# Mimi_layout.net
KiCad netlist of a schematic drawn in EAGLE
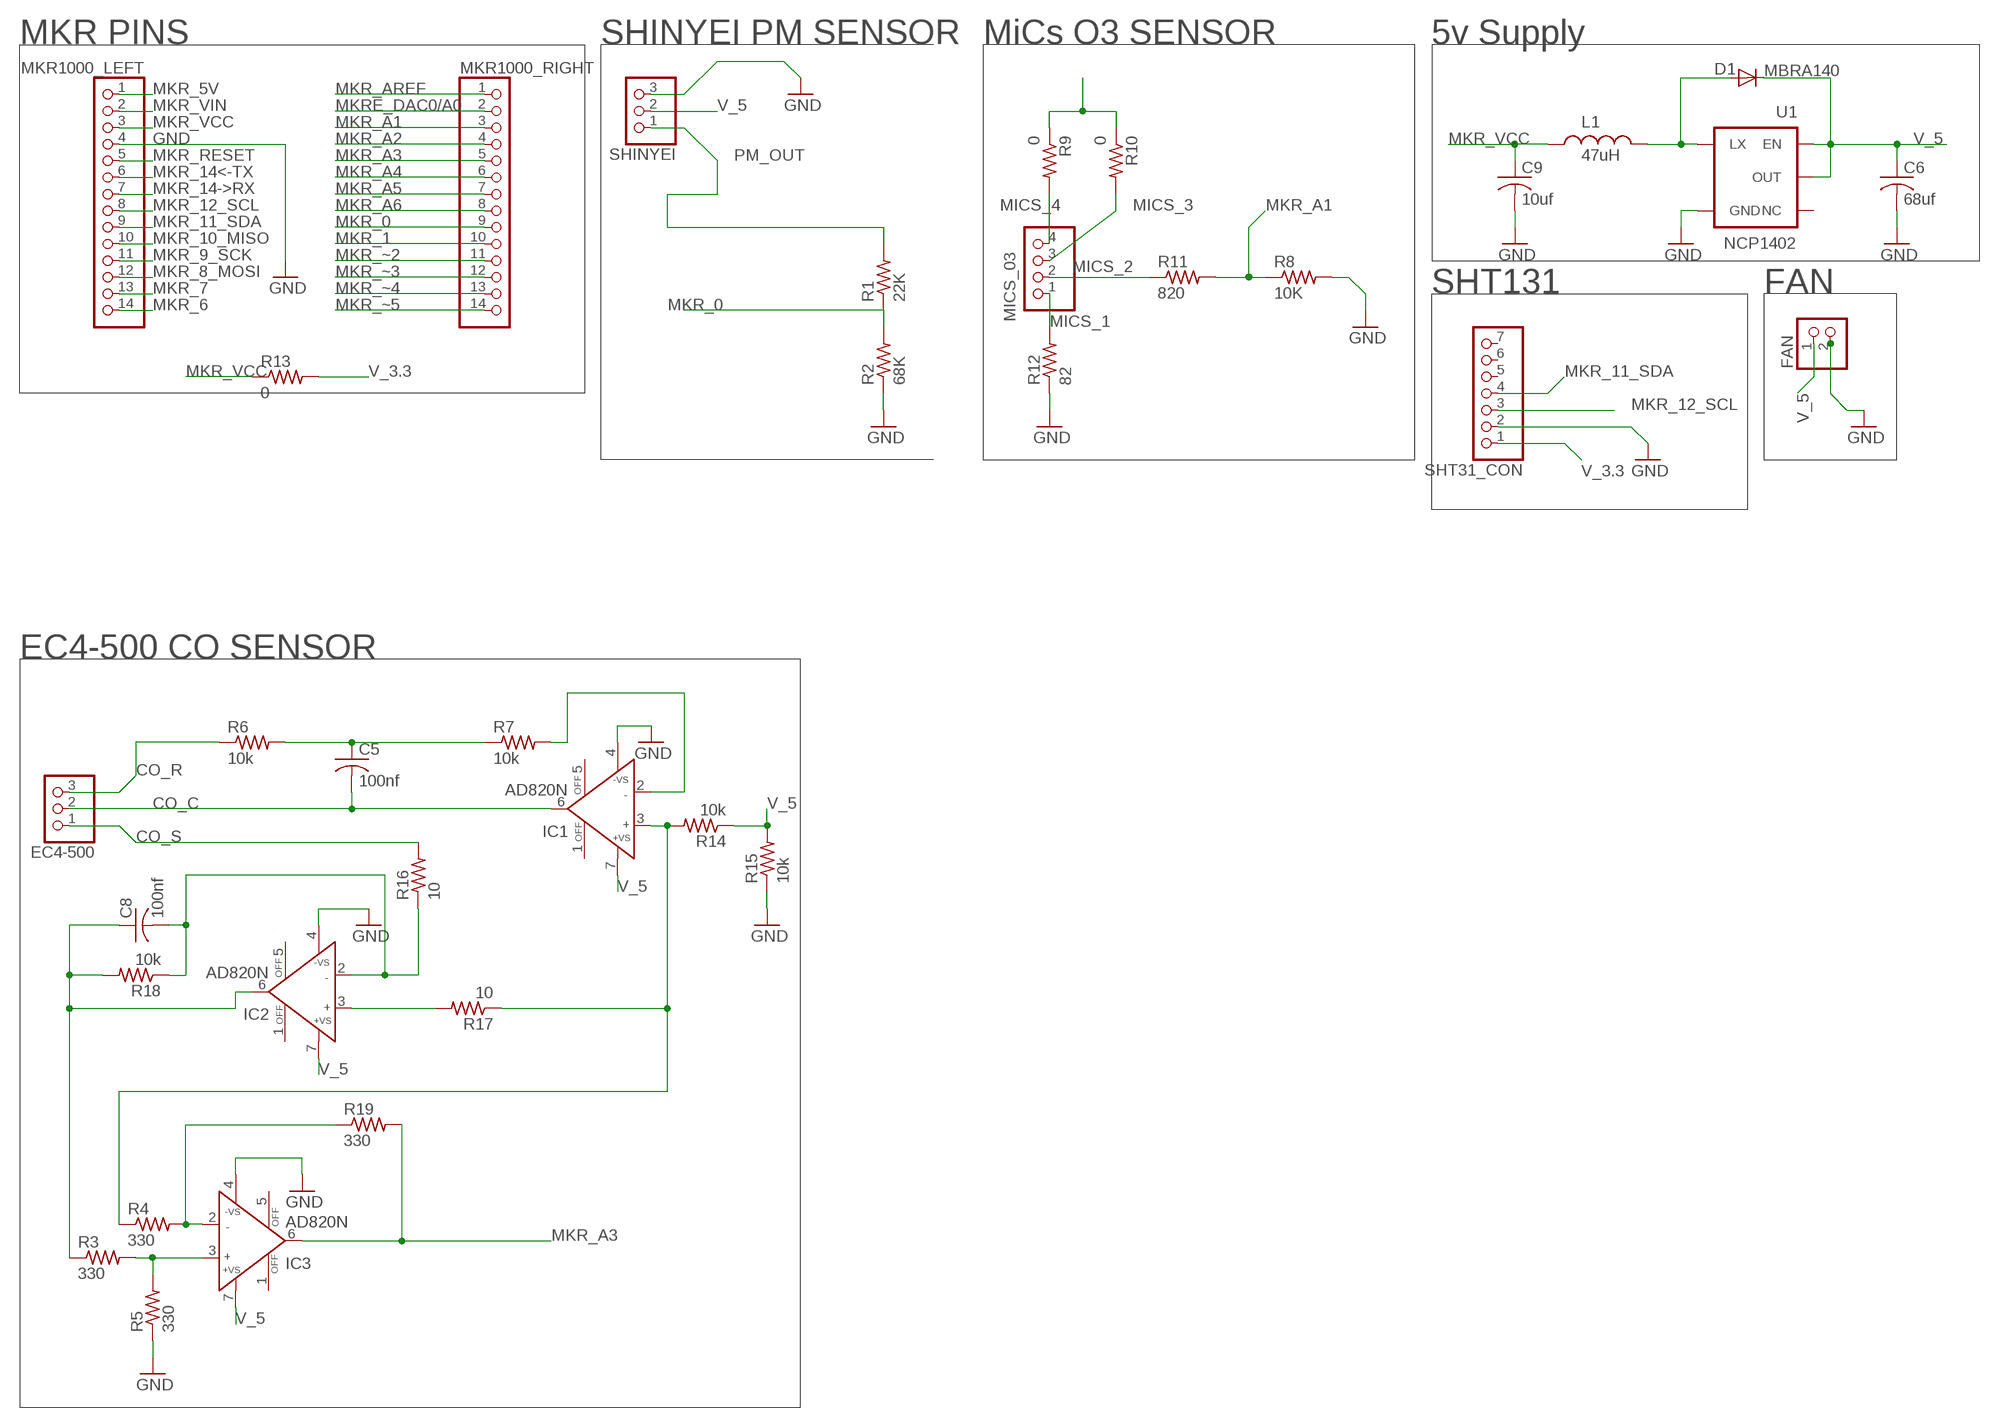
[diagram p0: schematic, sheet 1]

(export (version "E")
  (design (tool "Eeschema 10.0.6"))
  (components
    (comp (ref "C5")
      (value "100nf")
      (footprint "eagle-import:C0805")
      (libsource (lib "eagle-import") (part "C-USC0805"))
    )
    (comp (ref "C6")
      (value "68uf")
      (footprint "eagle-import:C0805")
      (libsource (lib "eagle-import") (part "C-USC0805"))
    )
    (comp (ref "C8")
      (value "100nf")
      (footprint "eagle-import:C0805")
      (libsource (lib "eagle-import") (part "C-USC0805"))
    )
    (comp (ref "C9")
      (value "10uf")
      (footprint "eagle-import:C0805")
      (libsource (lib "eagle-import") (part "C-USC0805"))
    )
    (comp (ref "D1")
      (value "MBRA140")
      (footprint "eagle-import:SMA-DIODE")
      (libsource (lib "eagle-import") (part "DIODESMA"))
    )
    (comp (ref "EC4-500")
      (value "PINHD-1X3")
      (footprint "eagle-import:1X03")
      (libsource (lib "eagle-import") (part "PINHD-1X3"))
    )
    (comp (ref "FAN")
      (value "PINHD-1X2")
      (footprint "eagle-import:1X02")
      (libsource (lib "eagle-import") (part "PINHD-1X2"))
    )
    (comp (ref "IC1")
      (value "AD820N")
      (footprint "eagle-import:DIL08")
      (libsource (lib "eagle-import") (part "AD820N"))
    )
    (comp (ref "IC2")
      (value "AD820N")
      (footprint "eagle-import:DIL08")
      (libsource (lib "eagle-import") (part "AD820N"))
    )
    (comp (ref "IC3")
      (value "AD820N")
      (footprint "eagle-import:DIL08")
      (libsource (lib "eagle-import") (part "AD820N"))
    )
    (comp (ref "L1")
      (value "47uH")
      (footprint "eagle-import:CR54")
      (libsource (lib "eagle-import") (part "INDUCTORCR54"))
    )
    (comp (ref "MICS_03")
      (value "PINHD-1X4")
      (footprint "eagle-import:1X04")
      (libsource (lib "eagle-import") (part "PINHD-1X4"))
    )
    (comp (ref "MKR1000_LEFT")
      (value "PINHD-1X14")
      (footprint "eagle-import:1X14")
      (libsource (lib "eagle-import") (part "PINHD-1X14"))
    )
    (comp (ref "MKR1000_RIGHT")
      (value "PINHD-1X14")
      (footprint "eagle-import:1X14")
      (libsource (lib "eagle-import") (part "PINHD-1X14"))
    )
    (comp (ref "R1")
      (value "22K")
      (footprint "eagle-import:R0805")
      (libsource (lib "eagle-import") (part "R-US_R0805"))
    )
    (comp (ref "R2")
      (value "68K")
      (footprint "eagle-import:R0805")
      (libsource (lib "eagle-import") (part "R-US_R0805"))
    )
    (comp (ref "R3")
      (value "330")
      (footprint "eagle-import:R0805")
      (libsource (lib "eagle-import") (part "R-US_R0805"))
    )
    (comp (ref "R4")
      (value "330")
      (footprint "eagle-import:R0805")
      (libsource (lib "eagle-import") (part "R-US_R0805"))
    )
    (comp (ref "R5")
      (value "330")
      (footprint "eagle-import:R0805")
      (libsource (lib "eagle-import") (part "R-US_R0805"))
    )
    (comp (ref "R6")
      (value "10k")
      (footprint "eagle-import:R0805")
      (libsource (lib "eagle-import") (part "R-US_R0805"))
    )
    (comp (ref "R7")
      (value "10k")
      (footprint "eagle-import:R0805")
      (libsource (lib "eagle-import") (part "R-US_R0805"))
    )
    (comp (ref "R8")
      (value "10K")
      (footprint "eagle-import:R0805")
      (libsource (lib "eagle-import") (part "R-US_R0805"))
    )
    (comp (ref "R9")
      (value "0")
      (footprint "eagle-import:R0805")
      (libsource (lib "eagle-import") (part "R-US_R0805"))
    )
    (comp (ref "R10")
      (value "0")
      (footprint "eagle-import:R0805")
      (libsource (lib "eagle-import") (part "R-US_R0805"))
    )
    (comp (ref "R11")
      (value "820")
      (footprint "eagle-import:R0805")
      (libsource (lib "eagle-import") (part "R-US_R0805"))
    )
    (comp (ref "R12")
      (value "82")
      (footprint "eagle-import:R0805")
      (libsource (lib "eagle-import") (part "R-US_R0805"))
    )
    (comp (ref "R13")
      (value "0")
      (footprint "eagle-import:R0805")
      (libsource (lib "eagle-import") (part "R-US_R0805"))
    )
    (comp (ref "R14")
      (value "10k")
      (footprint "eagle-import:R0805")
      (libsource (lib "eagle-import") (part "R-US_R0805"))
    )
    (comp (ref "R15")
      (value "10k")
      (footprint "eagle-import:R0805")
      (libsource (lib "eagle-import") (part "R-US_R0805"))
    )
    (comp (ref "R16")
      (value "10")
      (footprint "eagle-import:R0805")
      (libsource (lib "eagle-import") (part "R-US_R0805"))
    )
    (comp (ref "R17")
      (value "10")
      (footprint "eagle-import:R0805")
      (libsource (lib "eagle-import") (part "R-US_R0805"))
    )
    (comp (ref "R18")
      (value "10k")
      (footprint "eagle-import:R0805")
      (libsource (lib "eagle-import") (part "R-US_R0805"))
    )
    (comp (ref "R19")
      (value "330")
      (footprint "eagle-import:R0805")
      (libsource (lib "eagle-import") (part "R-US_R0805"))
    )
    (comp (ref "SHINYEI")
      (value "PINHD-1X3")
      (footprint "eagle-import:1X03")
      (libsource (lib "eagle-import") (part "PINHD-1X3"))
    )
    (comp (ref "SHT31_CON")
      (value "PINHD-1X7")
      (footprint "eagle-import:1X07")
      (libsource (lib "eagle-import") (part "PINHD-1X7"))
    )
    (comp (ref "U1")
      (value "NCP1402")
      (footprint "eagle-import:SOT23-5")
      (libsource (lib "eagle-import") (part "V_REG_NCP1400SOT23-5"))
    )
  )
  (nets
    (net (code "1") (name "CO_C") (class "Default")
      (node (ref "C5") (pin "2") (pinfunction "2_2") (pintype "passive"))
      (node (ref "EC4-500") (pin "2") (pinfunction "2_2") (pintype "passive"))
      (node (ref "IC1") (pin "6") (pinfunction "OUT_6") (pintype "output"))
    )
    (net (code "2") (name "CO_R") (class "Default")
      (node (ref "EC4-500") (pin "3") (pinfunction "3_3") (pintype "passive"))
      (node (ref "R6") (pin "1") (pinfunction "1_1") (pintype "passive"))
    )
    (net (code "3") (name "CO_S") (class "Default")
      (node (ref "EC4-500") (pin "1") (pinfunction "1_1") (pintype "passive"))
      (node (ref "R16") (pin "2") (pinfunction "2_2") (pintype "passive"))
    )
    (net (code "4") (name "GND") (class "Default")
      (node (ref "C6") (pin "2") (pinfunction "2_2") (pintype "passive"))
      (node (ref "C9") (pin "2") (pinfunction "2_2") (pintype "passive"))
      (node (ref "FAN") (pin "2") (pinfunction "2_2") (pintype "passive"))
      (node (ref "IC1") (pin "4") (pinfunction "-VS_4") (pintype "input"))
      (node (ref "IC2") (pin "4") (pinfunction "-VS_4") (pintype "input"))
      (node (ref "IC3") (pin "4") (pinfunction "-VS_4") (pintype "input"))
      (node (ref "MKR1000_LEFT") (pin "4") (pinfunction "4_4") (pintype "passive"))
      (node (ref "R12") (pin "1") (pinfunction "1_1") (pintype "passive"))
      (node (ref "R15") (pin "1") (pinfunction "1_1") (pintype "passive"))
      (node (ref "R2") (pin "1") (pinfunction "1_1") (pintype "passive"))
      (node (ref "R5") (pin "1") (pinfunction "1_1") (pintype "passive"))
      (node (ref "R8") (pin "2") (pinfunction "2_2") (pintype "passive"))
      (node (ref "SHINYEI") (pin "3") (pinfunction "3_3") (pintype "passive"))
      (node (ref "SHT31_CON") (pin "2") (pinfunction "2_2") (pintype "passive"))
      (node (ref "U1") (pin "4") (pinfunction "GND_4") (pintype "input"))
    )
    (net (code "5") (name "MICS_1") (class "Default")
      (node (ref "MICS_03") (pin "1") (pinfunction "1_1") (pintype "passive"))
      (node (ref "R12") (pin "2") (pinfunction "2_2") (pintype "passive"))
    )
    (net (code "6") (name "MICS_2") (class "Default")
      (node (ref "MICS_03") (pin "2") (pinfunction "2_2") (pintype "passive"))
      (node (ref "R11") (pin "1") (pinfunction "1_1") (pintype "passive"))
    )
    (net (code "7") (name "MICS_3") (class "Default")
      (node (ref "MICS_03") (pin "3") (pinfunction "3_3") (pintype "passive"))
      (node (ref "R10") (pin "2") (pinfunction "2_2") (pintype "passive"))
    )
    (net (code "8") (name "MICS_4") (class "Default")
      (node (ref "MICS_03") (pin "4") (pinfunction "4_4") (pintype "passive"))
      (node (ref "R9") (pin "2") (pinfunction "2_2") (pintype "passive"))
    )
    (net (code "9") (name "MKRE_DAC0{slash}A0") (class "Default")
      (node (ref "MKR1000_RIGHT") (pin "2") (pinfunction "2_2") (pintype "passive"))
    )
    (net (code "10") (name "MKR_0") (class "Default")
      (node (ref "MKR1000_RIGHT") (pin "9") (pinfunction "9_9") (pintype "passive"))
      (node (ref "R1") (pin "1") (pinfunction "1_1") (pintype "passive"))
      (node (ref "R2") (pin "2") (pinfunction "2_2") (pintype "passive"))
    )
    (net (code "11") (name "MKR_1") (class "Default")
      (node (ref "MKR1000_RIGHT") (pin "10") (pinfunction "10_10") (pintype "passive"))
    )
    (net (code "12") (name "MKR_5V") (class "Default")
      (node (ref "MKR1000_LEFT") (pin "1") (pinfunction "1_1") (pintype "passive"))
    )
    (net (code "13") (name "MKR_6") (class "Default")
      (node (ref "MKR1000_LEFT") (pin "14") (pinfunction "14_14") (pintype "passive"))
    )
    (net (code "14") (name "MKR_7") (class "Default")
      (node (ref "MKR1000_LEFT") (pin "13") (pinfunction "13_13") (pintype "passive"))
    )
    (net (code "15") (name "MKR_8_MOSI") (class "Default")
      (node (ref "MKR1000_LEFT") (pin "12") (pinfunction "12_12") (pintype "passive"))
    )
    (net (code "16") (name "MKR_9_SCK") (class "Default")
      (node (ref "MKR1000_LEFT") (pin "11") (pinfunction "11_11") (pintype "passive"))
    )
    (net (code "17") (name "MKR_10_MISO") (class "Default")
      (node (ref "MKR1000_LEFT") (pin "10") (pinfunction "10_10") (pintype "passive"))
    )
    (net (code "18") (name "MKR_11_SDA") (class "Default")
      (node (ref "MKR1000_LEFT") (pin "9") (pinfunction "9_9") (pintype "passive"))
      (node (ref "SHT31_CON") (pin "4") (pinfunction "4_4") (pintype "passive"))
    )
    (net (code "19") (name "MKR_12_SCL") (class "Default")
      (node (ref "MKR1000_LEFT") (pin "8") (pinfunction "8_8") (pintype "passive"))
      (node (ref "SHT31_CON") (pin "3") (pinfunction "3_3") (pintype "passive"))
    )
    (net (code "20") (name "MKR_14->RX") (class "Default")
      (node (ref "MKR1000_LEFT") (pin "7") (pinfunction "7_7") (pintype "passive"))
    )
    (net (code "21") (name "MKR_14<-TX") (class "Default")
      (node (ref "MKR1000_LEFT") (pin "6") (pinfunction "6_6") (pintype "passive"))
    )
    (net (code "22") (name "MKR_A1") (class "Default")
      (node (ref "MKR1000_RIGHT") (pin "3") (pinfunction "3_3") (pintype "passive"))
      (node (ref "R11") (pin "2") (pinfunction "2_2") (pintype "passive"))
      (node (ref "R8") (pin "1") (pinfunction "1_1") (pintype "passive"))
    )
    (net (code "23") (name "MKR_A2") (class "Default")
      (node (ref "MKR1000_RIGHT") (pin "4") (pinfunction "4_4") (pintype "passive"))
    )
    (net (code "24") (name "MKR_A3") (class "Default")
      (node (ref "IC3") (pin "6") (pinfunction "OUT_6") (pintype "output"))
      (node (ref "MKR1000_RIGHT") (pin "5") (pinfunction "5_5") (pintype "passive"))
      (node (ref "R19") (pin "2") (pinfunction "2_2") (pintype "passive"))
    )
    (net (code "25") (name "MKR_A4") (class "Default")
      (node (ref "MKR1000_RIGHT") (pin "6") (pinfunction "6_6") (pintype "passive"))
    )
    (net (code "26") (name "MKR_A5") (class "Default")
      (node (ref "MKR1000_RIGHT") (pin "7") (pinfunction "7_7") (pintype "passive"))
    )
    (net (code "27") (name "MKR_A6") (class "Default")
      (node (ref "MKR1000_RIGHT") (pin "8") (pinfunction "8_8") (pintype "passive"))
    )
    (net (code "28") (name "MKR_AREF") (class "Default")
      (node (ref "MKR1000_RIGHT") (pin "1") (pinfunction "1_1") (pintype "passive"))
    )
    (net (code "29") (name "MKR_RESET") (class "Default")
      (node (ref "MKR1000_LEFT") (pin "5") (pinfunction "5_5") (pintype "passive"))
    )
    (net (code "30") (name "MKR_VCC") (class "Default")
      (node (ref "C9") (pin "1") (pinfunction "1_1") (pintype "passive"))
      (node (ref "L1") (pin "P$1") (pinfunction "1_P$1") (pintype "passive"))
      (node (ref "MKR1000_LEFT") (pin "3") (pinfunction "3_3") (pintype "passive"))
      (node (ref "R13") (pin "1") (pinfunction "1_1") (pintype "passive"))
    )
    (net (code "31") (name "MKR_VIN") (class "Default")
      (node (ref "MKR1000_LEFT") (pin "2") (pinfunction "2_2") (pintype "passive"))
    )
    (net (code "32") (name "MKR_~{2}") (class "Default")
      (node (ref "MKR1000_RIGHT") (pin "11") (pinfunction "11_11") (pintype "passive"))
    )
    (net (code "33") (name "MKR_~{3}") (class "Default")
      (node (ref "MKR1000_RIGHT") (pin "12") (pinfunction "12_12") (pintype "passive"))
    )
    (net (code "34") (name "MKR_~{4}") (class "Default")
      (node (ref "MKR1000_RIGHT") (pin "13") (pinfunction "13_13") (pintype "passive"))
    )
    (net (code "35") (name "MKR_~{5}") (class "Default")
      (node (ref "MKR1000_RIGHT") (pin "14") (pinfunction "14_14") (pintype "passive"))
    )
    (net (code "36") (name "Net-(C5-Pad1)") (class "Default")
      (node (ref "C5") (pin "1") (pinfunction "1_1") (pintype "passive"))
      (node (ref "R6") (pin "2") (pinfunction "2_2") (pintype "passive"))
      (node (ref "R7") (pin "1") (pinfunction "1_1") (pintype "passive"))
    )
    (net (code "37") (name "Net-(IC1-IN+)") (class "Default")
      (node (ref "IC1") (pin "3") (pinfunction "IN+_3") (pintype "input"))
      (node (ref "R14") (pin "2") (pinfunction "2_2") (pintype "passive"))
      (node (ref "R17") (pin "1") (pinfunction "1_1") (pintype "passive"))
      (node (ref "R4") (pin "1") (pinfunction "1_1") (pintype "passive"))
    )
    (net (code "38") (name "Net-(IC1-IN-)") (class "Default")
      (node (ref "IC1") (pin "2") (pinfunction "IN-_2") (pintype "input"))
      (node (ref "R7") (pin "2") (pinfunction "2_2") (pintype "passive"))
    )
    (net (code "39") (name "Net-(IC2-IN+)") (class "Default")
      (node (ref "IC2") (pin "3") (pinfunction "IN+_3") (pintype "input"))
      (node (ref "R17") (pin "2") (pinfunction "2_2") (pintype "passive"))
    )
    (net (code "40") (name "Net-(IC2-IN-)") (class "Default")
      (node (ref "C8") (pin "2") (pinfunction "2_2") (pintype "passive"))
      (node (ref "IC2") (pin "2") (pinfunction "IN-_2") (pintype "input"))
      (node (ref "R16") (pin "1") (pinfunction "1_1") (pintype "passive"))
      (node (ref "R18") (pin "1") (pinfunction "1_1") (pintype "passive"))
    )
    (net (code "41") (name "Net-(IC2-OUT)") (class "Default")
      (node (ref "C8") (pin "1") (pinfunction "1_1") (pintype "passive"))
      (node (ref "IC2") (pin "6") (pinfunction "OUT_6") (pintype "output"))
      (node (ref "R18") (pin "2") (pinfunction "2_2") (pintype "passive"))
      (node (ref "R3") (pin "1") (pinfunction "1_1") (pintype "passive"))
    )
    (net (code "42") (name "Net-(IC3-IN+)") (class "Default")
      (node (ref "IC3") (pin "3") (pinfunction "IN+_3") (pintype "input"))
      (node (ref "R3") (pin "2") (pinfunction "2_2") (pintype "passive"))
      (node (ref "R5") (pin "2") (pinfunction "2_2") (pintype "passive"))
    )
    (net (code "43") (name "Net-(IC3-IN-)") (class "Default")
      (node (ref "IC3") (pin "2") (pinfunction "IN-_2") (pintype "input"))
      (node (ref "R19") (pin "1") (pinfunction "1_1") (pintype "passive"))
      (node (ref "R4") (pin "2") (pinfunction "2_2") (pintype "passive"))
    )
    (net (code "44") (name "Net-(L1-2)") (class "Default")
      (node (ref "D1") (pin "A") (pinfunction "A_A") (pintype "passive"))
      (node (ref "L1") (pin "P$2") (pinfunction "2_P$2") (pintype "passive"))
      (node (ref "U1") (pin "5") (pinfunction "LX_5") (pintype "input"))
    )
    (net (code "45") (name "PM_OUT") (class "Default")
      (node (ref "R1") (pin "2") (pinfunction "2_2") (pintype "passive"))
      (node (ref "SHINYEI") (pin "1") (pinfunction "1_1") (pintype "passive"))
    )
    (net (code "46") (name "V_3.3") (class "Default")
      (node (ref "R13") (pin "2") (pinfunction "2_2") (pintype "passive"))
      (node (ref "SHT31_CON") (pin "1") (pinfunction "1_1") (pintype "passive"))
    )
    (net (code "47") (name "V_5") (class "Default")
      (node (ref "C6") (pin "1") (pinfunction "1_1") (pintype "passive"))
      (node (ref "D1") (pin "C") (pinfunction "C_C") (pintype "passive"))
      (node (ref "FAN") (pin "1") (pinfunction "1_1") (pintype "passive"))
      (node (ref "IC1") (pin "7") (pinfunction "+VS_7") (pintype "input"))
      (node (ref "IC2") (pin "7") (pinfunction "+VS_7") (pintype "input"))
      (node (ref "IC3") (pin "7") (pinfunction "+VS_7") (pintype "input"))
      (node (ref "R10") (pin "1") (pinfunction "1_1") (pintype "passive"))
      (node (ref "R14") (pin "1") (pinfunction "1_1") (pintype "passive"))
      (node (ref "R15") (pin "2") (pinfunction "2_2") (pintype "passive"))
      (node (ref "R9") (pin "1") (pinfunction "1_1") (pintype "passive"))
      (node (ref "SHINYEI") (pin "2") (pinfunction "2_2") (pintype "passive"))
      (node (ref "U1") (pin "1") (pinfunction "EN_1") (pintype "input"))
      (node (ref "U1") (pin "2") (pinfunction "OUT_2") (pintype "passive"))
    )
    (net (code "48") (name "unconnected-(IC1-OFF-Pad1)") (class "Default")
      (node (ref "IC1") (pin "1") (pinfunction "OFF_1") (pintype "passive"))
    )
    (net (code "49") (name "unconnected-(IC1-OFF-Pad5)") (class "Default")
      (node (ref "IC1") (pin "5") (pinfunction "OFF_5") (pintype "passive"))
    )
    (net (code "50") (name "unconnected-(IC2-OFF-Pad1)") (class "Default")
      (node (ref "IC2") (pin "1") (pinfunction "OFF_1") (pintype "passive"))
    )
    (net (code "51") (name "unconnected-(IC2-OFF-Pad5)") (class "Default")
      (node (ref "IC2") (pin "5") (pinfunction "OFF_5") (pintype "passive"))
    )
    (net (code "52") (name "unconnected-(IC3-OFF-Pad1)") (class "Default")
      (node (ref "IC3") (pin "1") (pinfunction "OFF_1") (pintype "passive"))
    )
    (net (code "53") (name "unconnected-(IC3-OFF-Pad5)") (class "Default")
      (node (ref "IC3") (pin "5") (pinfunction "OFF_5") (pintype "passive"))
    )
    (net (code "54") (name "unconnected-(SHT31_CON-Pad5)") (class "Default")
      (node (ref "SHT31_CON") (pin "5") (pinfunction "5_5") (pintype "passive"))
    )
    (net (code "55") (name "unconnected-(SHT31_CON-Pad6)") (class "Default")
      (node (ref "SHT31_CON") (pin "6") (pinfunction "6_6") (pintype "passive"))
    )
    (net (code "56") (name "unconnected-(SHT31_CON-Pad7)") (class "Default")
      (node (ref "SHT31_CON") (pin "7") (pinfunction "7_7") (pintype "passive"))
    )
    (net (code "57") (name "unconnected-(U1-NC-Pad3)") (class "Default")
      (node (ref "U1") (pin "3") (pinfunction "NC_3") (pintype "input"))
    )
  )
)
